# dldpad_schematic.net
KiCad netlist of a schematic drawn in EasyEDA
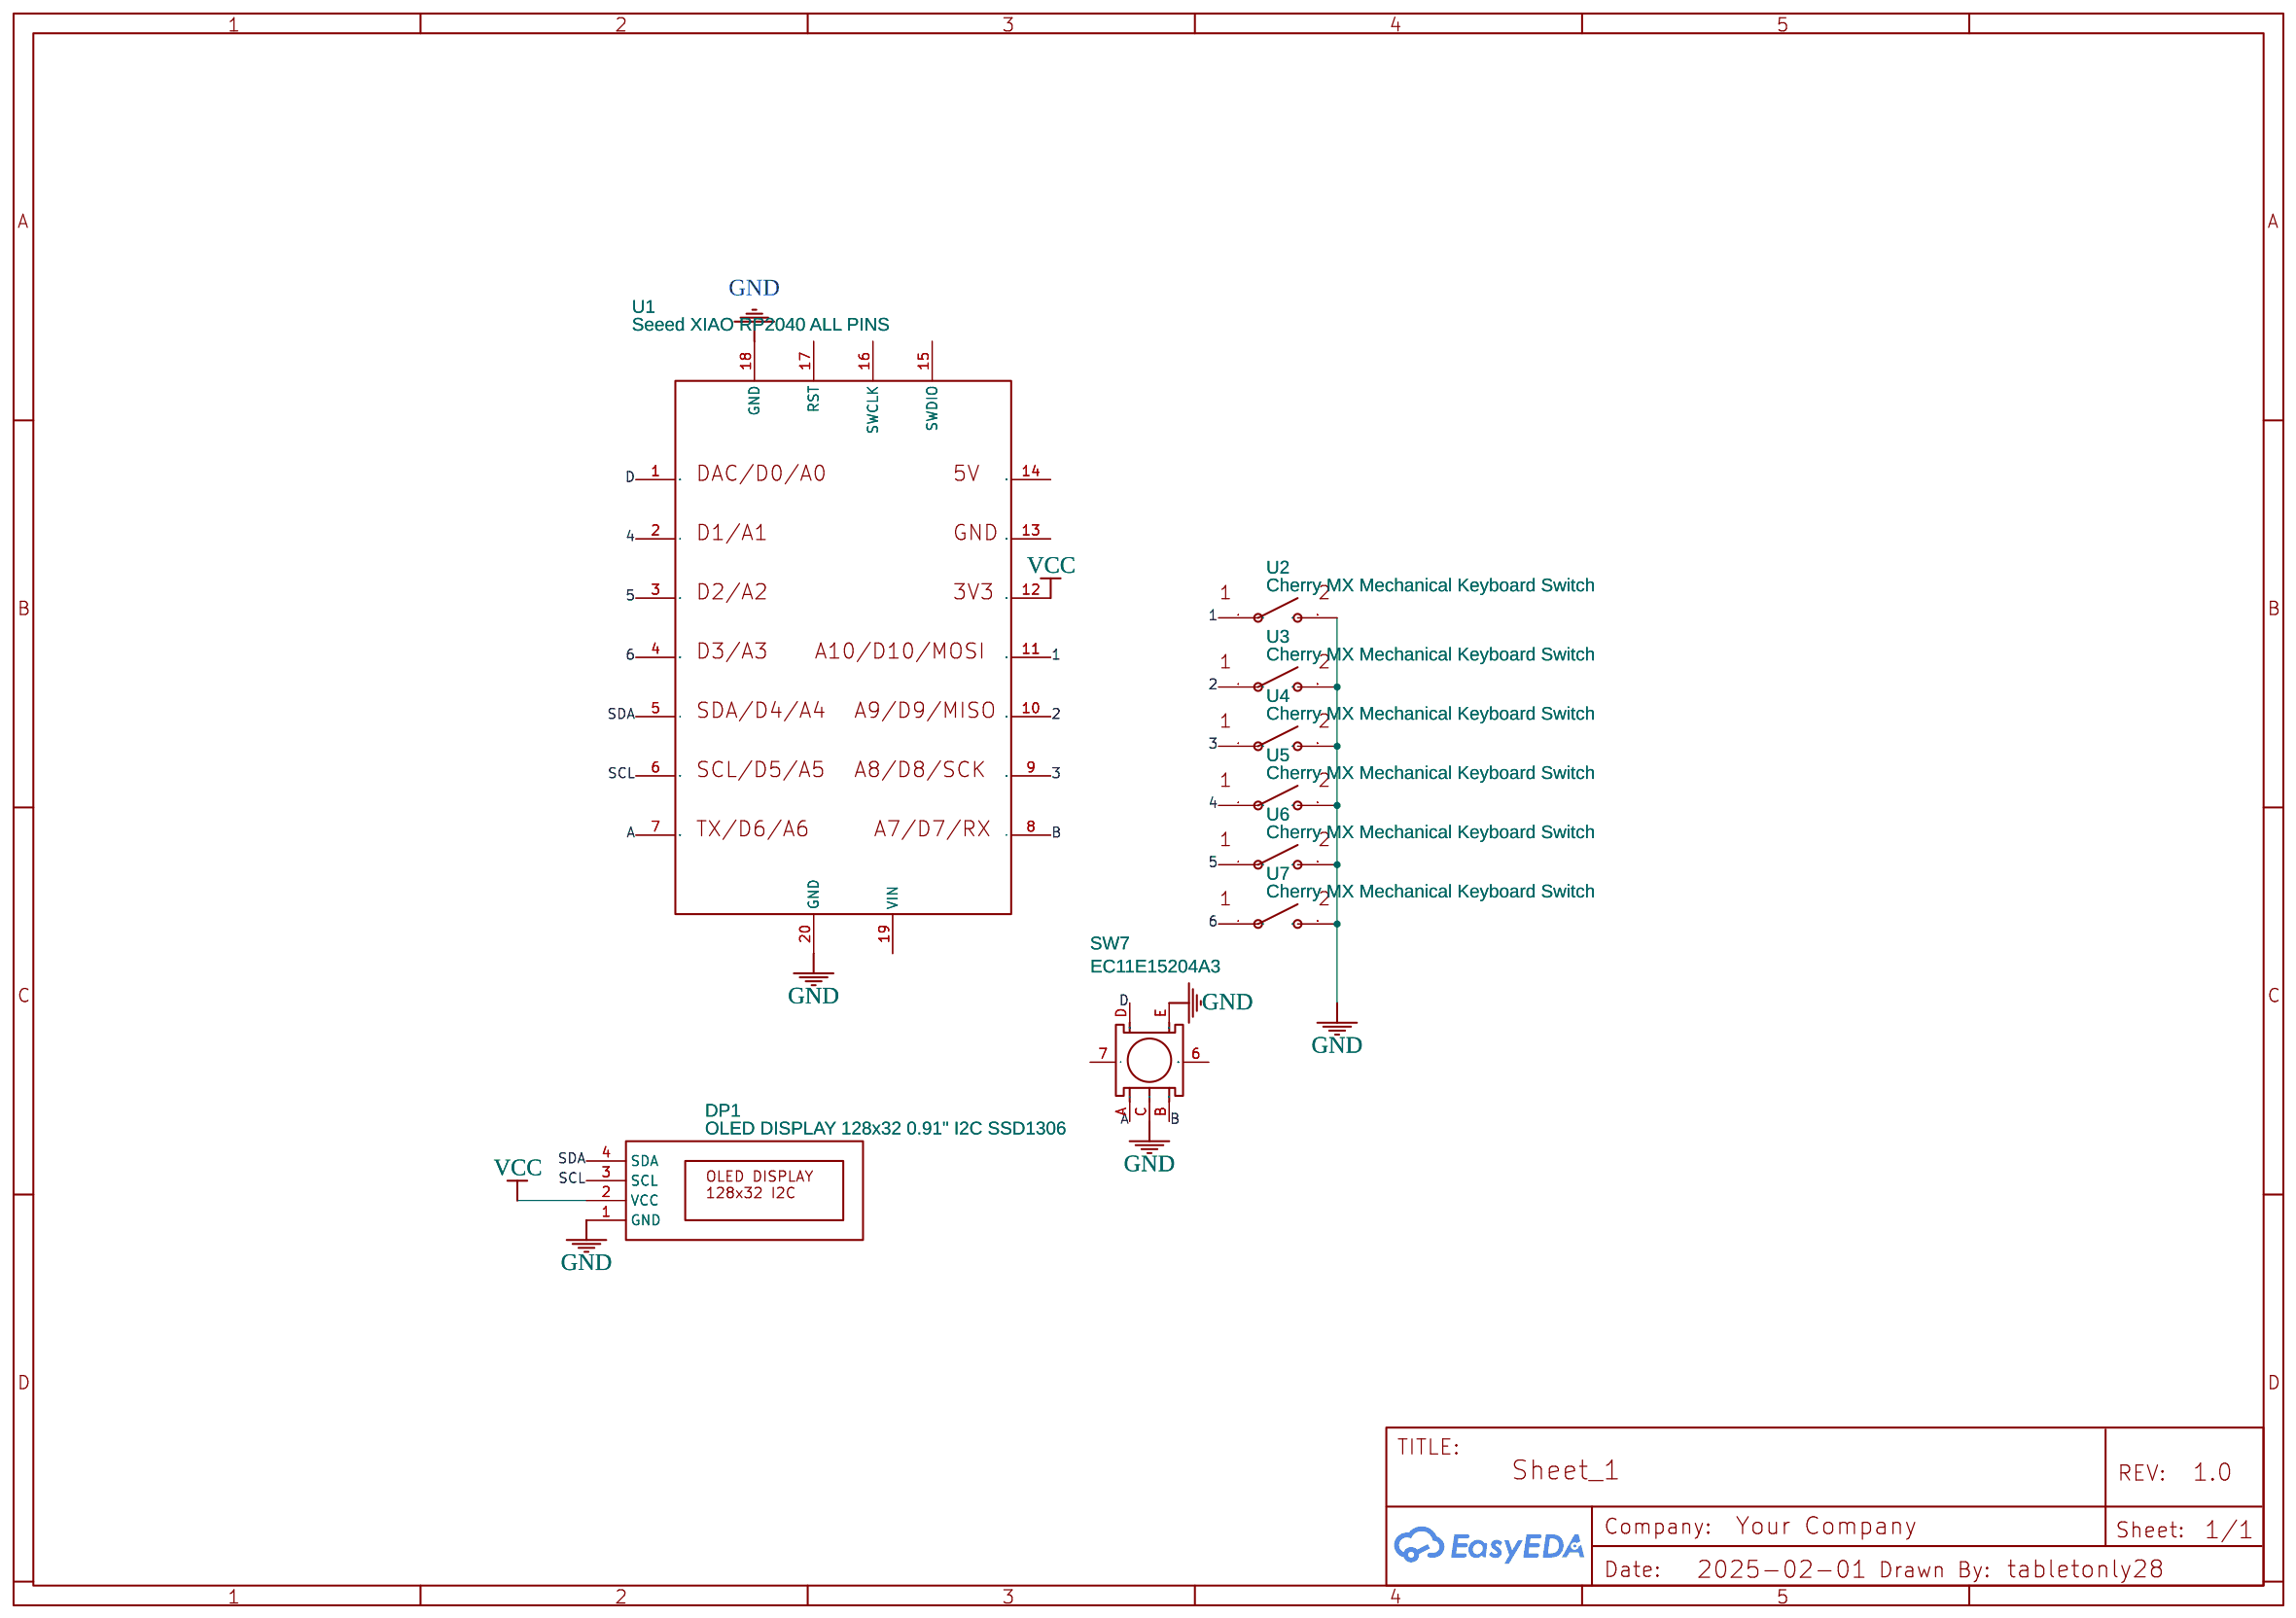
[diagram p0: schematic sheet]

(export (version "E")
  (design (tool "Eeschema 10.0.6"))
  (components
    (comp (ref "DP1")
      (value "OLED DISPLAY 128x32 0.91\" I2C SSD1306")
      (libsource (lib "") (part "OLED DISPLAY 128x32 0.91{dblquote} I2C SSD1306"))
    )
    (comp (ref "SW7")
      (value "EC11E15204A3")
      (fields (field (name "Manufacturer") "ALPSALPINE(阿尔卑斯阿尔派)"))
      (libsource (lib "") (part "EC11E15204A3"))
    )
    (comp (ref "U1")
      (value "Seeed XIAO RP2040 ALL PINS")
      (fields (field (name "Manufacturer Part") "102010328") (field (name "Manufacturer") "Seeedstudio"))
      (libsource (lib "") (part "Seeed XIAO RP2040 ALL PINS"))
    )
    (comp (ref "U2")
      (value "Cherry MX Mechanical Keyboard Switch")
      (libsource (lib "") (part "Cherry MX Mechanical Keyboard Switch"))
    )
    (comp (ref "U3")
      (value "Cherry MX Mechanical Keyboard Switch")
      (libsource (lib "") (part "Cherry MX Mechanical Keyboard Switch"))
    )
    (comp (ref "U4")
      (value "Cherry MX Mechanical Keyboard Switch")
      (libsource (lib "") (part "Cherry MX Mechanical Keyboard Switch"))
    )
    (comp (ref "U5")
      (value "Cherry MX Mechanical Keyboard Switch")
      (libsource (lib "") (part "Cherry MX Mechanical Keyboard Switch"))
    )
    (comp (ref "U6")
      (value "Cherry MX Mechanical Keyboard Switch")
      (libsource (lib "") (part "Cherry MX Mechanical Keyboard Switch"))
    )
    (comp (ref "U7")
      (value "Cherry MX Mechanical Keyboard Switch")
      (libsource (lib "") (part "Cherry MX Mechanical Keyboard Switch"))
    )
  )
  (nets
    (net (code "1") (name "/1") (class "Default")
      (node (ref "U1") (pin "11") (pinfunction "10_11") (pintype "unspecified"))
      (node (ref "U2") (pin "1") (pinfunction "1_1") (pintype "unspecified"))
    )
    (net (code "2") (name "/2") (class "Default")
      (node (ref "U1") (pin "10") (pinfunction "9_10") (pintype "unspecified"))
      (node (ref "U3") (pin "1") (pinfunction "1_1") (pintype "unspecified"))
    )
    (net (code "3") (name "/3") (class "Default")
      (node (ref "U1") (pin "9") (pinfunction "8_9") (pintype "unspecified"))
      (node (ref "U4") (pin "1") (pinfunction "1_1") (pintype "unspecified"))
    )
    (net (code "4") (name "/4") (class "Default")
      (node (ref "U1") (pin "2") (pinfunction "1_2") (pintype "unspecified"))
      (node (ref "U5") (pin "1") (pinfunction "1_1") (pintype "unspecified"))
    )
    (net (code "5") (name "/5") (class "Default")
      (node (ref "U1") (pin "3") (pinfunction "2_3") (pintype "unspecified"))
      (node (ref "U6") (pin "1") (pinfunction "1_1") (pintype "unspecified"))
    )
    (net (code "6") (name "/6") (class "Default")
      (node (ref "U1") (pin "4") (pinfunction "3_4") (pintype "unspecified"))
      (node (ref "U7") (pin "1") (pinfunction "1_1") (pintype "unspecified"))
    )
    (net (code "7") (name "/A") (class "Default")
      (node (ref "SW7") (pin "A") (pinfunction "A_A") (pintype "unspecified"))
      (node (ref "U1") (pin "7") (pinfunction "6_7") (pintype "unspecified"))
    )
    (net (code "8") (name "/B") (class "Default")
      (node (ref "SW7") (pin "B") (pinfunction "B_B") (pintype "unspecified"))
      (node (ref "U1") (pin "8") (pinfunction "7_8") (pintype "unspecified"))
    )
    (net (code "9") (name "/D") (class "Default")
      (node (ref "SW7") (pin "D") (pinfunction "D_D") (pintype "unspecified"))
      (node (ref "U1") (pin "1") (pinfunction "0_1") (pintype "unspecified"))
    )
    (net (code "10") (name "/SCL") (class "Default")
      (node (ref "DP1") (pin "3") (pinfunction "SCL_3") (pintype "input"))
      (node (ref "U1") (pin "6") (pinfunction "5_6") (pintype "unspecified"))
    )
    (net (code "11") (name "/SDA") (class "Default")
      (node (ref "DP1") (pin "4") (pinfunction "SDA_4") (pintype "input"))
      (node (ref "U1") (pin "5") (pinfunction "4_5") (pintype "unspecified"))
    )
    (net (code "12") (name "GND") (class "Default")
      (node (ref "DP1") (pin "1") (pinfunction "GND_1") (pintype "passive"))
      (node (ref "SW7") (pin "C") (pinfunction "C_C") (pintype "unspecified"))
      (node (ref "SW7") (pin "E") (pinfunction "E_E") (pintype "unspecified"))
      (node (ref "U1") (pin "18") (pinfunction "GND_18") (pintype "unspecified"))
      (node (ref "U1") (pin "20") (pinfunction "GND_20") (pintype "unspecified"))
      (node (ref "U2") (pin "2") (pinfunction "2_2") (pintype "unspecified"))
      (node (ref "U3") (pin "2") (pinfunction "2_2") (pintype "unspecified"))
      (node (ref "U4") (pin "2") (pinfunction "2_2") (pintype "unspecified"))
      (node (ref "U5") (pin "2") (pinfunction "2_2") (pintype "unspecified"))
      (node (ref "U6") (pin "2") (pinfunction "2_2") (pintype "unspecified"))
      (node (ref "U7") (pin "2") (pinfunction "2_2") (pintype "unspecified"))
    )
    (net (code "13") (name "VCC") (class "Default")
      (node (ref "DP1") (pin "2") (pinfunction "VCC_2") (pintype "passive"))
      (node (ref "U1") (pin "12") (pinfunction "11_12") (pintype "unspecified"))
    )
    (net (code "14") (name "unconnected-(SW7-Pad6)") (class "Default")
      (node (ref "SW7") (pin "6") (pinfunction "6_6") (pintype "unspecified"))
    )
    (net (code "15") (name "unconnected-(SW7-Pad7)") (class "Default")
      (node (ref "SW7") (pin "7") (pinfunction "7_7") (pintype "unspecified"))
    )
    (net (code "16") (name "unconnected-(U1-12-Pad13)") (class "Default")
      (node (ref "U1") (pin "13") (pinfunction "12_13") (pintype "unspecified"))
    )
    (net (code "17") (name "unconnected-(U1-13-Pad14)") (class "Default")
      (node (ref "U1") (pin "14") (pinfunction "13_14") (pintype "unspecified"))
    )
    (net (code "18") (name "unconnected-(U1-RST-Pad17)") (class "Default")
      (node (ref "U1") (pin "17") (pinfunction "RST_17") (pintype "unspecified"))
    )
    (net (code "19") (name "unconnected-(U1-SWCLK-Pad16)") (class "Default")
      (node (ref "U1") (pin "16") (pinfunction "SWCLK_16") (pintype "unspecified"))
    )
    (net (code "20") (name "unconnected-(U1-SWDIO-Pad15)") (class "Default")
      (node (ref "U1") (pin "15") (pinfunction "SWDIO_15") (pintype "unspecified"))
    )
    (net (code "21") (name "unconnected-(U1-VIN-Pad19)") (class "Default")
      (node (ref "U1") (pin "19") (pinfunction "VIN_19") (pintype "unspecified"))
    )
  )
)
